# Power.net
KiCad netlist of a schematic drawn in Altium Designer
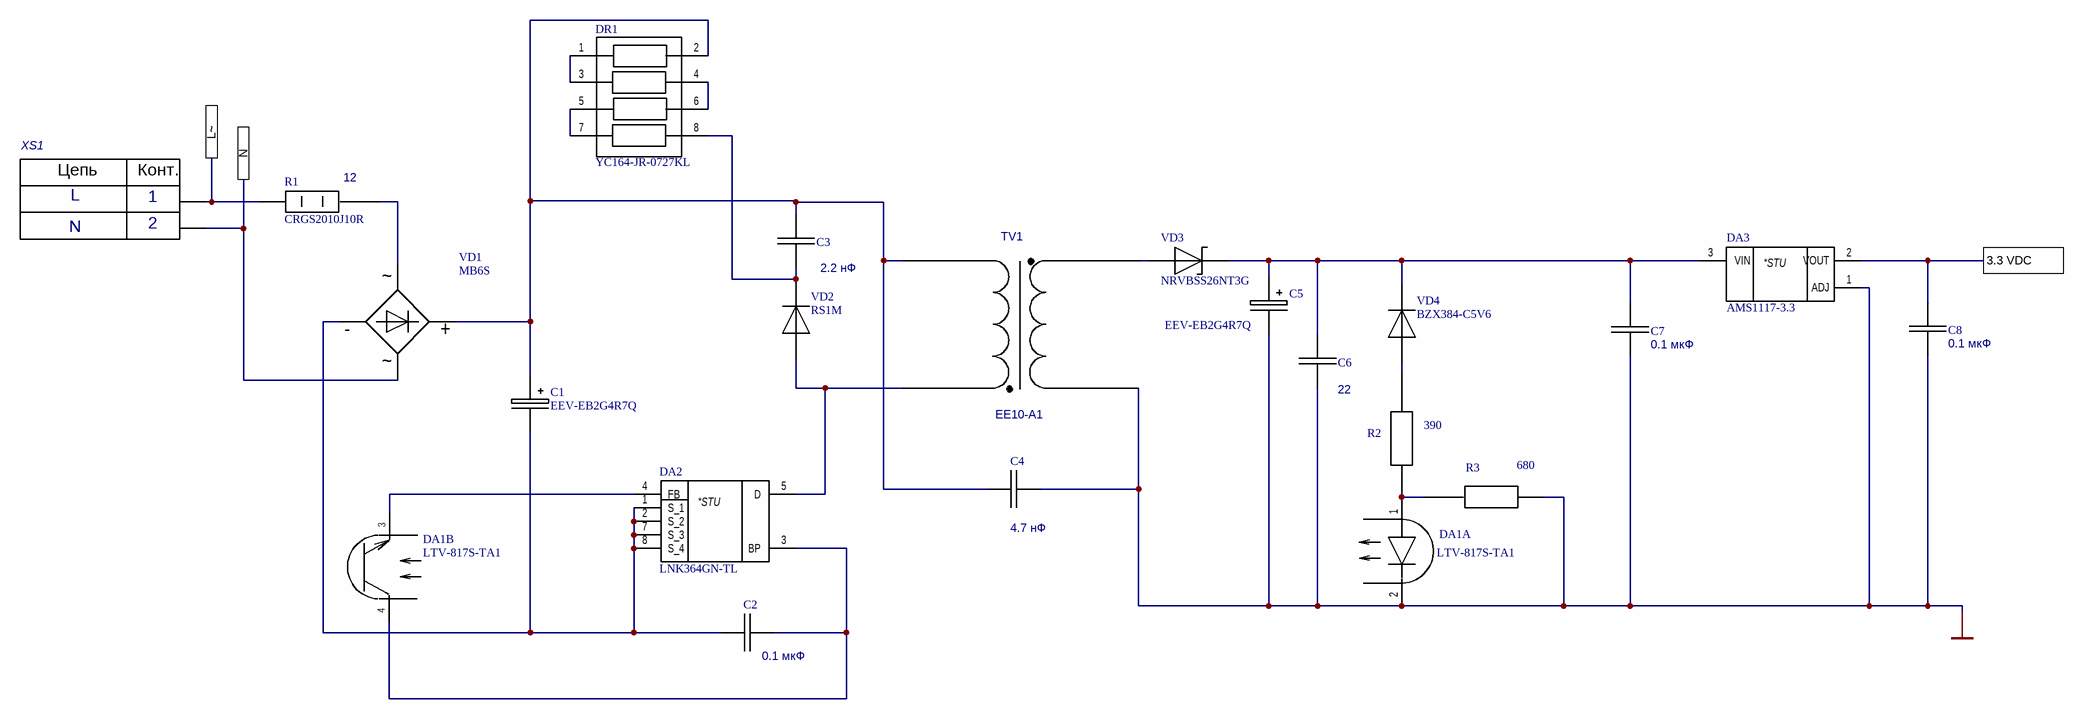
[diagram p0: Power.SchDoc]

(export (version "E")
  (design (tool "Eeschema 10.0.6"))
  (components
    (comp (ref "C1")
      (value "EEV-EB2G4R7Q")
      (footprint "Termal controller:CAPAE1030X1700N")
      (description "Capacitor Polarised")
      (fields (field (name "MOUSER PART NUMBER") "667-EEV-EB2G4R7Q"))
      (libsource (lib "Termal controller") (part "EEV-EB2G4R7Q"))
    )
    (comp (ref "C2")
      (value "0.1 мкФ")
      (footprint "С0603")
      (description "Керамический ЧИП-конденсатор 0603 X7R 0.1мкФ ±5% 50В")
      (fields
        (field (name "MANUFACTURER_PART_NUMBER") "CC0402KRX7R7BB222")
        (field (name "Comment") "06035C104JAT2A")
      )
      (libsource (lib "") (part "Конденсатор неполярный_1"))
    )
    (comp (ref "C3")
      (value "2.2 нФ")
      (footprint "C1206")
      (description "Керамический ЧИП-конденсатор 1206 X7R 2200пФ ±10% 500В")
      (fields
        (field (name "MANUFACTURER_PART_NUMBER") "CC0402KRX7R7BB222")
        (field (name "Comment") "CC1206KKX7RBBB222")
      )
      (libsource (lib "Termal controller") (part "Конденсатор неполярный"))
    )
    (comp (ref "C4")
      (value "4.7 нФ")
      (footprint "B81123C1472M000")
      (description "Capacitor")
      (fields
        (field (name "MANUFACTURER_PART_NUMBER") "CC0402KRX7R7BB222")
        (field (name "Comment") "Конденсатор неполярный")
      )
      (libsource (lib "") (part "Конденсатор неполярный_1"))
    )
    (comp (ref "C5")
      (value "EEV-EB2G4R7Q")
      (footprint "Termal controller:CAPAE1030X1700N")
      (description "Capacitor Polarised")
      (fields (field (name "MOUSER PART NUMBER") "667-EEV-EB2G4R7Q"))
      (libsource (lib "Termal controller") (part "Конденсатор полярный"))
    )
    (comp (ref "C6")
      (value "22")
      (footprint "C1206")
      (description "Керамический ЧИП-конденсатор 1206 X5R 22мкФ ±10% 16В")
      (fields
        (field (name "MANUFACTURER_PART_NUMBER") "CC0402KRX7R7BB222")
        (field (name "Comment") "CC1206KKX5R7BB226")
      )
      (libsource (lib "Termal controller") (part "Конденсатор неполярный"))
    )
    (comp (ref "C7")
      (value "0.1 мкФ")
      (footprint "С0603")
      (description "Керамический ЧИП-конденсатор 0603 X7R 0.1мкФ ±5% 50В")
      (fields
        (field (name "MANUFACTURER_PART_NUMBER") "CC0402KRX7R7BB222")
        (field (name "Comment") "06035C104JAT2A")
      )
      (libsource (lib "Termal controller") (part "Конденсатор неполярный"))
    )
    (comp (ref "C8")
      (value "0.1 мкФ")
      (footprint "С0603")
      (description "Керамический ЧИП-конденсатор 0603 X7R 0.1мкФ ±5% 50В")
      (fields
        (field (name "MANUFACTURER_PART_NUMBER") "CC0402KRX7R7BB222")
        (field (name "Comment") "06035C104JAT2A")
      )
      (libsource (lib "Termal controller") (part "Конденсатор неполярный"))
    )
    (comp (ref "DA1")
      (value "LTV-817S-TA1")
      (footprint "Termal controller:SOP254P1016X400-4N")
      (description "Integrated Circuit")
      (fields (field (name "MOUSER PART NUMBER") "859-LTV-817S-TA1"))
      (libsource (lib "Termal controller") (part "LTV-817S-TA1"))
    )
    (comp (ref "DA2")
      (value "LNK364GN-TL")
      (footprint "Termal controller:LNK364GNTL")
      (description "AC-DC контроллер")
      (fields (field (name "MOUSER PART NUMBER") "869-LNK364GN-TL"))
      (libsource (lib "Termal controller") (part "LNK364GN-TL"))
    )
    (comp (ref "DA3")
      (value "AMS1117-3.3")
      (footprint "Termal controller:SOT229P700X180-4N")
      (description "Integrated Circuit")
      (libsource (lib "Termal controller") (part "AMS1117-3.3"))
    )
    (comp (ref "DR1")
      (value "YC164-JR-0727KL")
      (footprint "CAT161000F4")
      (description "Resistor Network")
      (fields
        (field (name "MANUFACTURER_PART_NUMBER") "CAT16-2702F4LF")
        (field (name "MOUSER PART NUMBER") "652-CAT16-2702F4LF")
      )
      (libsource (lib "Termal controller") (part "Резисторная сборка 4"))
    )
    (comp (ref "R1")
      (value "CRGS2010J10R")
      (footprint "Termal controller:RESC5025X65N")
      (description "Resistor")
      (fields (field (name "MOUSER PART NUMBER") "279-CRGS2010J10R") (field (name "ALTIUM_VALUE") "12"))
      (libsource (lib "Termal controller") (part "CRGS2010J10R"))
    )
    (comp (ref "R2")
      (value "390")
      (footprint "R0402")
      (description "Толстопленочный ЧИП-резистор 0402 390Ом ±1% 0.063Вт -55°С...+155°С")
      (fields (field (name "Comment") "RC0402FR-07390RL"))
      (libsource (lib "Termal controller") (part "Резистор"))
    )
    (comp (ref "R3")
      (value "680")
      (footprint "R0402")
      (description "олстопленочный ЧИП-резистор 0402 680Ом ±1% 0.063Вт -55°С...+155°С")
      (fields (field (name "Comment") "RC0402FR-07680RL"))
      (libsource (lib "Termal controller") (part "Резистор"))
    )
    (comp (ref "TV1")
      (value "EE10-A1")
      (footprint "EE10-A1")
      (description "Импульсный трансформатор 220V; 5-12V; P=1-3W; 100-200kHz")
      (libsource (lib "Termal controller") (part "EE10-A1"))
    )
    (comp (ref "VD1")
      (value "MB6S")
      (footprint "SOP250P700X190-4N")
      (description "Bridge Rectifier")
      (libsource (lib "Termal controller") (part "MB6S"))
    )
    (comp (ref "VD2")
      (value "RS1M")
      (footprint "Termal controller:DIOM5026X262N")
      (description "Diode")
      (libsource (lib "Termal controller") (part "RS1M"))
    )
    (comp (ref "VD3")
      (value "NRVBSS26NT3G")
      (footprint "Termal controller:DIOM5436X247N")
      (description "Schottky Diode")
      (fields (field (name "MOUSER PART NUMBER") "863-NRVBSS26NT3G"))
      (libsource (lib "Termal controller") (part "NRVBSS26NT3G"))
    )
    (comp (ref "VD4")
      (value "BZX384-C5V6")
      (footprint "Termal controller:SOD2512X110N")
      (description "Diode")
      (libsource (lib "Termal controller") (part "BZX384-C5V6"))
    )
    (comp (ref "XS1")
      (value "S2B-PH-K-S")
      (footprint "ED350V-02P")
      (description "Гнездо провод-плата;")
      (libsource (lib "Termal controller") (part "Разъем_1"))
    )
  )
  (nets
    (net (code "1") (name "/3.3 VDC") (class "Default")
      (node (ref "C8") (pin "1") (pinfunction "1_1") (pintype "passive"))
      (node (ref "DA3") (pin "2") (pinfunction "VOUT_2") (pintype "passive"))
    )
    (net (code "2") (name "/L~") (class "Default")
      (node (ref "R1") (pin "1") (pinfunction "1_1") (pintype "passive"))
      (node (ref "XS1") (pin "1") (pinfunction "*_1") (pintype "passive"))
    )
    (net (code "3") (name "/N") (class "Default")
      (node (ref "VD1") (pin "4") (pinfunction "~_4") (pintype "passive"))
      (node (ref "XS1") (pin "2") (pinfunction "*_2") (pintype "passive"))
    )
    (net (code "4") (name "DGND") (class "Default")
      (node (ref "C4") (pin "2") (pinfunction "2_2") (pintype "passive"))
      (node (ref "C5") (pin "2") (pinfunction "-_2") (pintype "passive"))
      (node (ref "C6") (pin "2") (pinfunction "2_2") (pintype "passive"))
      (node (ref "C7") (pin "1") (pinfunction "1_1") (pintype "passive"))
      (node (ref "C8") (pin "2") (pinfunction "2_2") (pintype "passive"))
      (node (ref "DA1") (pin "2") (pinfunction "CATHODE_2") (pintype "passive"))
      (node (ref "DA3") (pin "1") (pinfunction "ADJ_1") (pintype "passive"))
      (node (ref "R3") (pin "1") (pinfunction "1_1") (pintype "passive"))
      (node (ref "TV1") (pin "5") (pinfunction "5_5") (pintype "passive"))
    )
    (net (code "5") (name "Net-(C1-+)") (class "Default")
      (node (ref "C1") (pin "1") (pinfunction "+_1") (pintype "passive"))
      (node (ref "C3") (pin "1") (pinfunction "1_1") (pintype "passive"))
      (node (ref "C4") (pin "1") (pinfunction "1_1") (pintype "passive"))
      (node (ref "DR1") (pin "2") (pinfunction "2_2") (pintype "passive"))
      (node (ref "TV1") (pin "1") (pinfunction "Vin_1") (pintype "passive"))
      (node (ref "VD1") (pin "1") (pinfunction "+_1") (pintype "passive"))
    )
    (net (code "6") (name "Net-(C1--)") (class "Default")
      (node (ref "C1") (pin "2") (pinfunction "-_2") (pintype "passive"))
      (node (ref "C2") (pin "1") (pinfunction "1_1") (pintype "passive"))
      (node (ref "DA2") (pin "1") (pinfunction "S_1_1") (pintype "passive"))
      (node (ref "DA2") (pin "2") (pinfunction "S_2_2") (pintype "passive"))
      (node (ref "DA2") (pin "7") (pinfunction "S_3_7") (pintype "passive"))
      (node (ref "DA2") (pin "8") (pinfunction "S_4_8") (pintype "passive"))
      (node (ref "VD1") (pin "2") (pinfunction "-_2") (pintype "passive"))
    )
    (net (code "7") (name "Net-(C5-+)") (class "Default")
      (node (ref "C5") (pin "1") (pinfunction "+_1") (pintype "passive"))
      (node (ref "C6") (pin "1") (pinfunction "1_1") (pintype "passive"))
      (node (ref "C7") (pin "2") (pinfunction "2_2") (pintype "passive"))
      (node (ref "DA3") (pin "3") (pinfunction "VIN_3") (pintype "passive"))
      (node (ref "VD3") (pin "1") (pinfunction "K_1") (pintype "passive"))
      (node (ref "VD4") (pin "1") (pinfunction "K_1") (pintype "passive"))
    )
    (net (code "8") (name "Net-(DA1A-ANODE)") (class "Default")
      (node (ref "DA1") (pin "1") (pinfunction "ANODE_1") (pintype "passive"))
      (node (ref "R2") (pin "1") (pinfunction "1_1") (pintype "passive"))
      (node (ref "R3") (pin "2") (pinfunction "0_2") (pintype "passive"))
    )
    (net (code "9") (name "Net-(DA1B-C)") (class "Default")
      (node (ref "C2") (pin "2") (pinfunction "2_2") (pintype "passive"))
      (node (ref "DA1") (pin "4") (pinfunction "C_4") (pintype "passive"))
      (node (ref "DA2") (pin "3") (pinfunction "BP_3") (pintype "passive"))
    )
    (net (code "10") (name "Net-(DA1B-E)") (class "Default")
      (node (ref "DA1") (pin "3") (pinfunction "E_3") (pintype "passive"))
      (node (ref "DA2") (pin "4") (pinfunction "FB_4") (pintype "passive"))
    )
    (net (code "11") (name "Net-(DA2-D)") (class "Default")
      (node (ref "DA2") (pin "5") (pinfunction "D_5") (pintype "passive"))
      (node (ref "TV1") (pin "4") (pinfunction "4_4") (pintype "passive"))
      (node (ref "VD2") (pin "2") (pinfunction "A_2") (pintype "passive"))
    )
    (net (code "12") (name "Net-(DR1-Pad1)") (class "Default")
      (node (ref "DR1") (pin "1") (pinfunction "1_1") (pintype "passive"))
      (node (ref "DR1") (pin "3") (pinfunction "3_3") (pintype "passive"))
    )
    (net (code "13") (name "Net-(DR1-Pad4)") (class "Default")
      (node (ref "DR1") (pin "4") (pinfunction "4_4") (pintype "passive"))
      (node (ref "DR1") (pin "6") (pinfunction "6_6") (pintype "passive"))
    )
    (net (code "14") (name "Net-(DR1-Pad5)") (class "Default")
      (node (ref "DR1") (pin "5") (pinfunction "5_5") (pintype "passive"))
      (node (ref "DR1") (pin "7") (pinfunction "7_7") (pintype "passive"))
    )
    (net (code "15") (name "Net-(R1-0)") (class "Default")
      (node (ref "R1") (pin "2") (pinfunction "0_2") (pintype "passive"))
      (node (ref "VD1") (pin "3") (pinfunction "~_3") (pintype "passive"))
    )
    (net (code "16") (name "Net-(R2-0)") (class "Default")
      (node (ref "R2") (pin "2") (pinfunction "0_2") (pintype "passive"))
      (node (ref "VD4") (pin "2") (pinfunction "A_2") (pintype "passive"))
    )
    (net (code "17") (name "Net-(TV1-Vout)") (class "Default")
      (node (ref "TV1") (pin "8") (pinfunction "Vout_8") (pintype "passive"))
      (node (ref "VD3") (pin "2") (pinfunction "A_2") (pintype "passive"))
    )
    (net (code "18") (name "Net-(VD2-K)") (class "Default")
      (node (ref "C3") (pin "2") (pinfunction "2_2") (pintype "passive"))
      (node (ref "DR1") (pin "8") (pinfunction "8_8") (pintype "passive"))
      (node (ref "VD2") (pin "1") (pinfunction "K_1") (pintype "passive"))
    )
  )
)
